# Headphone.net
KiCad netlist of a schematic drawn in EAGLE
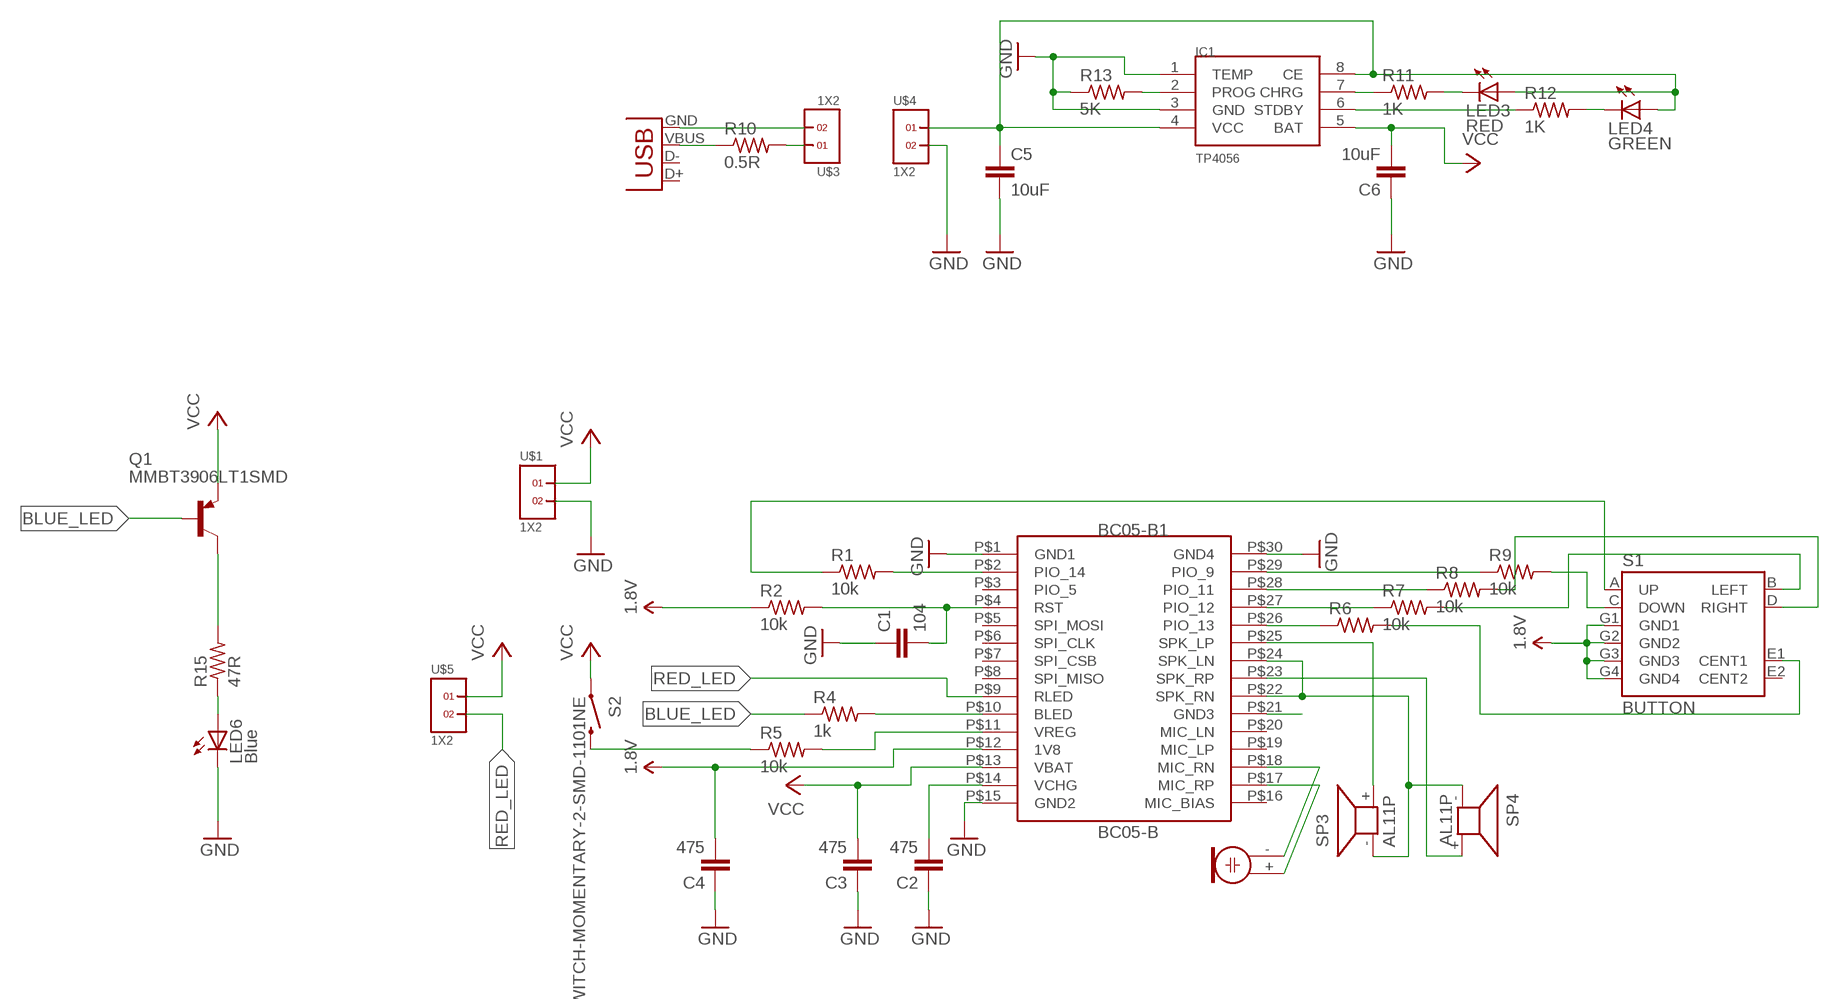
[diagram p0: schematic, sheet 1]

(export (version "E")
  (design (tool "Eeschema 10.0.6"))
  (components
    (comp (ref "BC05-B1")
      (value "BC05-B")
      (footprint "eagle-import:BC05-B")
      (libsource (lib "eagle-import") (part "BC05-B"))
    )
    (comp (ref "C1")
      (value "104")
      (footprint "eagle-import:C0603K")
      (libsource (lib "eagle-import") (part "C-EUC0603K"))
    )
    (comp (ref "C2")
      (value "475")
      (footprint "eagle-import:C0603K")
      (libsource (lib "eagle-import") (part "C-EUC0603K"))
    )
    (comp (ref "C3")
      (value "475")
      (footprint "eagle-import:C0603K")
      (libsource (lib "eagle-import") (part "C-EUC0603K"))
    )
    (comp (ref "C4")
      (value "475")
      (footprint "eagle-import:C0603K")
      (libsource (lib "eagle-import") (part "C-EUC0603K"))
    )
    (comp (ref "C5")
      (value "10uF")
      (footprint "eagle-import:C0805K")
      (libsource (lib "eagle-import") (part "C-EUC0805K"))
    )
    (comp (ref "C6")
      (value "10uF")
      (footprint "eagle-import:C0805K")
      (libsource (lib "eagle-import") (part "C-EUC0805K"))
    )
    (comp (ref "IC1")
      (value "TP4056")
      (footprint "eagle-import:SOP-8")
      (libsource (lib "eagle-import") (part "TP4056"))
    )
    (comp (ref "LED3")
      (value "RED")
      (footprint "eagle-import:CHIP-LED0805")
      (libsource (lib "eagle-import") (part "LEDCHIP-LED0805"))
    )
    (comp (ref "LED4")
      (value "GREEN")
      (footprint "eagle-import:CHIP-LED0805")
      (libsource (lib "eagle-import") (part "LEDCHIP-LED0805"))
    )
    (comp (ref "LED6")
      (value "Blue")
      (footprint "eagle-import:CHIP-LED0805")
      (libsource (lib "eagle-import") (part "LEDCHIP-LED0805"))
    )
    (comp (ref "M1")
      (value "ELECTRET_MICROPHON-TOM-1545P-R")
      (footprint "eagle-import:TOM-1545P-R")
      (libsource (lib "eagle-import") (part "ELECTRET_MICROPHON-TOM-1545P-R"))
    )
    (comp (ref "Q1")
      (value "MMBT3906LT1SMD")
      (footprint "eagle-import:SOT23-BEC")
      (libsource (lib "eagle-import") (part "MMBT3906SMDLT1"))
    )
    (comp (ref "R1")
      (value "10k")
      (footprint "eagle-import:R0603")
      (libsource (lib "eagle-import") (part "R-US_R0603"))
    )
    (comp (ref "R2")
      (value "10k")
      (footprint "eagle-import:R0603")
      (libsource (lib "eagle-import") (part "R-US_R0603"))
    )
    (comp (ref "R4")
      (value "1k")
      (footprint "eagle-import:R0603")
      (libsource (lib "eagle-import") (part "R-US_R0603"))
    )
    (comp (ref "R5")
      (value "10k")
      (footprint "eagle-import:R0603")
      (libsource (lib "eagle-import") (part "R-US_R0603"))
    )
    (comp (ref "R6")
      (value "10k")
      (footprint "eagle-import:R0603")
      (libsource (lib "eagle-import") (part "R-US_R0603"))
    )
    (comp (ref "R7")
      (value "10k")
      (footprint "eagle-import:R0603")
      (libsource (lib "eagle-import") (part "R-US_R0603"))
    )
    (comp (ref "R8")
      (value "10k")
      (footprint "eagle-import:R0603")
      (libsource (lib "eagle-import") (part "R-US_R0603"))
    )
    (comp (ref "R9")
      (value "10k")
      (footprint "eagle-import:R0603")
      (libsource (lib "eagle-import") (part "R-US_R0603"))
    )
    (comp (ref "R10")
      (value "0.5R")
      (footprint "eagle-import:M0805")
      (libsource (lib "eagle-import") (part "R-US_M0805"))
    )
    (comp (ref "R11")
      (value "1K")
      (footprint "eagle-import:R0603")
      (libsource (lib "eagle-import") (part "R-US_R0603"))
    )
    (comp (ref "R12")
      (value "1K")
      (footprint "eagle-import:R0603")
      (libsource (lib "eagle-import") (part "R-US_R0603"))
    )
    (comp (ref "R13")
      (value "5K")
      (footprint "eagle-import:R0603")
      (libsource (lib "eagle-import") (part "R-US_R0603"))
    )
    (comp (ref "R15")
      (value "47R")
      (footprint "eagle-import:R0603")
      (libsource (lib "eagle-import") (part "R-US_R0603"))
    )
    (comp (ref "S1")
      (value "BUTTON")
      (footprint "eagle-import:BUTTON")
      (libsource (lib "eagle-import") (part "BUTTON"))
    )
    (comp (ref "S2")
      (value "SWITCH-MOMENTARY-2-SMD-1101NE")
      (footprint "eagle-import:TACTILE-SWITCH-1101NE")
      (libsource (lib "eagle-import") (part "SWITCH-MOMENTARY-2-SMD-1101NE"))
    )
    (comp (ref "SP3")
      (value "AL11P")
      (footprint "eagle-import:AL11P")
      (libsource (lib "eagle-import") (part "AL11P"))
    )
    (comp (ref "SP4")
      (value "AL11P")
      (footprint "eagle-import:AL11P")
      (libsource (lib "eagle-import") (part "AL11P"))
    )
    (comp (ref "U$1")
      (value "1X2")
      (footprint "eagle-import:1X2")
      (libsource (lib "eagle-import") (part "1X2"))
    )
    (comp (ref "U$3")
      (value "1X2")
      (footprint "eagle-import:1X2")
      (libsource (lib "eagle-import") (part "1X2"))
    )
    (comp (ref "U$4")
      (value "1X2")
      (footprint "eagle-import:1X2")
      (libsource (lib "eagle-import") (part "1X2"))
    )
    (comp (ref "U$5")
      (value "1X2")
      (footprint "eagle-import:1X2")
      (libsource (lib "eagle-import") (part "1X2"))
    )
    (comp (ref "X1")
      (value "USB-MICROB")
      (footprint "eagle-import:USB-MICROB")
      (libsource (lib "eagle-import") (part "USB-MICROB"))
    )
  )
  (nets
    (net (code "1") (name "1.8V") (class "Default")
      (node (ref "BC05-B1") (pin "P$12") (pinfunction "1V8_P$12") (pintype "bidirectional"))
      (node (ref "C4") (pin "2") (pinfunction "2_2") (pintype "passive"))
      (node (ref "R2") (pin "1") (pinfunction "1_1") (pintype "passive"))
      (node (ref "S1") (pin "G1") (pinfunction "GND1_G1") (pintype "bidirectional"))
      (node (ref "S1") (pin "G2") (pinfunction "GND2_G2") (pintype "bidirectional"))
      (node (ref "S1") (pin "G3") (pinfunction "GND3_G3") (pintype "bidirectional"))
      (node (ref "S1") (pin "G4") (pinfunction "GND4_G4") (pintype "bidirectional"))
    )
    (net (code "2") (name "BLUE_LED") (class "Default")
      (node (ref "Q1") (pin "B") (pinfunction "B_B") (pintype "passive"))
      (node (ref "R4") (pin "1") (pinfunction "1_1") (pintype "passive"))
    )
    (net (code "3") (name "GND") (class "Default")
      (node (ref "BC05-B1") (pin "P$1") (pinfunction "GND1_P$1") (pintype "bidirectional"))
      (node (ref "BC05-B1") (pin "P$15") (pinfunction "GND2_P$15") (pintype "bidirectional"))
      (node (ref "BC05-B1") (pin "P$30") (pinfunction "GND4_P$30") (pintype "bidirectional"))
      (node (ref "C1") (pin "1") (pinfunction "1_1") (pintype "passive"))
      (node (ref "C2") (pin "1") (pinfunction "1_1") (pintype "passive"))
      (node (ref "C3") (pin "1") (pinfunction "1_1") (pintype "passive"))
      (node (ref "C4") (pin "1") (pinfunction "1_1") (pintype "passive"))
      (node (ref "C5") (pin "2") (pinfunction "2_2") (pintype "passive"))
      (node (ref "C6") (pin "1") (pinfunction "1_1") (pintype "passive"))
      (node (ref "IC1") (pin "1") (pinfunction "TEMP_1") (pintype "bidirectional"))
      (node (ref "IC1") (pin "3") (pinfunction "GND_3") (pintype "bidirectional"))
      (node (ref "LED6") (pin "C") (pinfunction "C_C") (pintype "passive"))
      (node (ref "R13") (pin "1") (pinfunction "1_1") (pintype "passive"))
      (node (ref "U$1") (pin "2") (pinfunction "2_2") (pintype "bidirectional"))
      (node (ref "U$4") (pin "2") (pinfunction "2_2") (pintype "bidirectional"))
    )
    (net (code "4") (name "Net-(BC05-B1-BLED)") (class "Default")
      (node (ref "BC05-B1") (pin "P$10") (pinfunction "BLED_P$10") (pintype "bidirectional"))
      (node (ref "R4") (pin "2") (pinfunction "2_2") (pintype "passive"))
    )
    (net (code "5") (name "Net-(BC05-B1-MIC_RN)") (class "Default")
      (node (ref "BC05-B1") (pin "P$18") (pinfunction "MIC_RN_P$18") (pintype "bidirectional"))
      (node (ref "M1") (pin "-") (pinfunction "2_-") (pintype "passive"))
    )
    (net (code "6") (name "Net-(BC05-B1-MIC_RP)") (class "Default")
      (node (ref "BC05-B1") (pin "P$17") (pinfunction "MIC_RP_P$17") (pintype "bidirectional"))
      (node (ref "M1") (pin "+") (pinfunction "1_+") (pintype "passive"))
    )
    (net (code "7") (name "Net-(BC05-B1-PIO_9)") (class "Default")
      (node (ref "BC05-B1") (pin "P$29") (pinfunction "PIO_9_P$29") (pintype "bidirectional"))
      (node (ref "R9") (pin "1") (pinfunction "1_1") (pintype "passive"))
    )
    (net (code "8") (name "Net-(BC05-B1-PIO_11)") (class "Default")
      (node (ref "BC05-B1") (pin "P$28") (pinfunction "PIO_11_P$28") (pintype "bidirectional"))
      (node (ref "R8") (pin "1") (pinfunction "1_1") (pintype "passive"))
    )
    (net (code "9") (name "Net-(BC05-B1-PIO_12)") (class "Default")
      (node (ref "BC05-B1") (pin "P$27") (pinfunction "PIO_12_P$27") (pintype "bidirectional"))
      (node (ref "R7") (pin "1") (pinfunction "1_1") (pintype "passive"))
    )
    (net (code "10") (name "Net-(BC05-B1-PIO_13)") (class "Default")
      (node (ref "BC05-B1") (pin "P$26") (pinfunction "PIO_13_P$26") (pintype "bidirectional"))
      (node (ref "R6") (pin "1") (pinfunction "1_1") (pintype "passive"))
    )
    (net (code "11") (name "Net-(BC05-B1-PIO_14)") (class "Default")
      (node (ref "BC05-B1") (pin "P$2") (pinfunction "PIO_14_P$2") (pintype "bidirectional"))
      (node (ref "R1") (pin "2") (pinfunction "2_2") (pintype "passive"))
    )
    (net (code "12") (name "Net-(BC05-B1-RST)") (class "Default")
      (node (ref "BC05-B1") (pin "P$4") (pinfunction "RST_P$4") (pintype "bidirectional"))
      (node (ref "C1") (pin "2") (pinfunction "2_2") (pintype "passive"))
      (node (ref "R2") (pin "2") (pinfunction "2_2") (pintype "passive"))
    )
    (net (code "13") (name "Net-(BC05-B1-SPK_LN)") (class "Default")
      (node (ref "BC05-B1") (pin "P$22") (pinfunction "SPK_RN_P$22") (pintype "bidirectional"))
      (node (ref "BC05-B1") (pin "P$24") (pinfunction "SPK_LN_P$24") (pintype "bidirectional"))
      (node (ref "SP3") (pin "-") (pinfunction "1_-") (pintype "passive"))
      (node (ref "SP4") (pin "-") (pinfunction "1_-") (pintype "passive"))
    )
    (net (code "14") (name "Net-(BC05-B1-SPK_LP)") (class "Default")
      (node (ref "BC05-B1") (pin "P$25") (pinfunction "SPK_LP_P$25") (pintype "bidirectional"))
      (node (ref "SP3") (pin "+") (pinfunction "2_+") (pintype "passive"))
    )
    (net (code "15") (name "Net-(BC05-B1-SPK_RP)") (class "Default")
      (node (ref "BC05-B1") (pin "P$23") (pinfunction "SPK_RP_P$23") (pintype "bidirectional"))
      (node (ref "SP4") (pin "+") (pinfunction "2_+") (pintype "passive"))
    )
    (net (code "16") (name "Net-(BC05-B1-VCHG)") (class "Default")
      (node (ref "BC05-B1") (pin "P$14") (pinfunction "VCHG_P$14") (pintype "bidirectional"))
      (node (ref "C2") (pin "2") (pinfunction "2_2") (pintype "passive"))
    )
    (net (code "17") (name "Net-(BC05-B1-VREG)") (class "Default")
      (node (ref "BC05-B1") (pin "P$11") (pinfunction "VREG_P$11") (pintype "bidirectional"))
      (node (ref "R5") (pin "2") (pinfunction "2_2") (pintype "passive"))
    )
    (net (code "18") (name "Net-(IC1-CE)") (class "Default")
      (node (ref "C5") (pin "1") (pinfunction "1_1") (pintype "passive"))
      (node (ref "IC1") (pin "4") (pinfunction "VCC_4") (pintype "bidirectional"))
      (node (ref "IC1") (pin "8") (pinfunction "CE_8") (pintype "bidirectional"))
      (node (ref "LED3") (pin "A") (pinfunction "A_A") (pintype "passive"))
      (node (ref "LED4") (pin "A") (pinfunction "A_A") (pintype "passive"))
      (node (ref "U$4") (pin "1") (pinfunction "1_1") (pintype "bidirectional"))
    )
    (net (code "19") (name "Net-(IC1-CHRG)") (class "Default")
      (node (ref "IC1") (pin "7") (pinfunction "CHRG_7") (pintype "bidirectional"))
      (node (ref "R11") (pin "1") (pinfunction "1_1") (pintype "passive"))
    )
    (net (code "20") (name "Net-(IC1-PROG)") (class "Default")
      (node (ref "IC1") (pin "2") (pinfunction "PROG_2") (pintype "bidirectional"))
      (node (ref "R13") (pin "2") (pinfunction "2_2") (pintype "passive"))
    )
    (net (code "21") (name "Net-(IC1-STDBY)") (class "Default")
      (node (ref "IC1") (pin "6") (pinfunction "STDBY_6") (pintype "bidirectional"))
      (node (ref "R12") (pin "1") (pinfunction "1_1") (pintype "passive"))
    )
    (net (code "22") (name "Net-(LED3-PadC)") (class "Default")
      (node (ref "LED3") (pin "C") (pinfunction "C_C") (pintype "passive"))
      (node (ref "R11") (pin "2") (pinfunction "2_2") (pintype "passive"))
    )
    (net (code "23") (name "Net-(LED4-PadC)") (class "Default")
      (node (ref "LED4") (pin "C") (pinfunction "C_C") (pintype "passive"))
      (node (ref "R12") (pin "2") (pinfunction "2_2") (pintype "passive"))
    )
    (net (code "24") (name "Net-(LED6-PadA)") (class "Default")
      (node (ref "LED6") (pin "A") (pinfunction "A_A") (pintype "passive"))
      (node (ref "R15") (pin "1") (pinfunction "1_1") (pintype "passive"))
    )
    (net (code "25") (name "Net-(Q1-PadC)") (class "Default")
      (node (ref "Q1") (pin "C") (pinfunction "C_C") (pintype "passive"))
      (node (ref "R15") (pin "2") (pinfunction "2_2") (pintype "passive"))
    )
    (net (code "26") (name "Net-(R10-Pad1)") (class "Default")
      (node (ref "R10") (pin "1") (pinfunction "1_1") (pintype "passive"))
      (node (ref "X1") (pin "VBUS") (pinfunction "VBUS_VBUS") (pintype "bidirectional"))
    )
    (net (code "27") (name "Net-(R10-Pad2)") (class "Default")
      (node (ref "R10") (pin "2") (pinfunction "2_2") (pintype "passive"))
      (node (ref "U$3") (pin "1") (pinfunction "1_1") (pintype "bidirectional"))
    )
    (net (code "28") (name "Net-(S1-CENT1)") (class "Default")
      (node (ref "R6") (pin "2") (pinfunction "2_2") (pintype "passive"))
      (node (ref "S1") (pin "E1") (pinfunction "CENT1_E1") (pintype "bidirectional"))
    )
    (net (code "29") (name "Net-(S1-DOWN)") (class "Default")
      (node (ref "R9") (pin "2") (pinfunction "2_2") (pintype "passive"))
      (node (ref "S1") (pin "C") (pinfunction "DOWN_C") (pintype "bidirectional"))
    )
    (net (code "30") (name "Net-(S1-LEFT)") (class "Default")
      (node (ref "R7") (pin "2") (pinfunction "2_2") (pintype "passive"))
      (node (ref "S1") (pin "B") (pinfunction "LEFT_B") (pintype "bidirectional"))
    )
    (net (code "31") (name "Net-(S1-RIGHT)") (class "Default")
      (node (ref "R8") (pin "2") (pinfunction "2_2") (pintype "passive"))
      (node (ref "S1") (pin "D") (pinfunction "RIGHT_D") (pintype "bidirectional"))
    )
    (net (code "32") (name "Net-(S1-UP)") (class "Default")
      (node (ref "R1") (pin "1") (pinfunction "1_1") (pintype "passive"))
      (node (ref "S1") (pin "A") (pinfunction "UP_A") (pintype "bidirectional"))
    )
    (net (code "33") (name "Net-(S2-2)") (class "Default")
      (node (ref "R5") (pin "1") (pinfunction "1_1") (pintype "passive"))
      (node (ref "S2") (pin "P$2") (pinfunction "2_P$2") (pintype "passive"))
    )
    (net (code "34") (name "Net-(U$3-Pad2)") (class "Default")
      (node (ref "U$3") (pin "2") (pinfunction "2_2") (pintype "bidirectional"))
      (node (ref "X1") (pin "GND") (pinfunction "GND_GND") (pintype "bidirectional"))
    )
    (net (code "35") (name "RED_LED") (class "Default")
      (node (ref "BC05-B1") (pin "P$9") (pinfunction "RLED_P$9") (pintype "bidirectional"))
      (node (ref "U$5") (pin "2") (pinfunction "2_2") (pintype "bidirectional"))
    )
    (net (code "36") (name "VCC") (class "Default")
      (node (ref "BC05-B1") (pin "P$13") (pinfunction "VBAT_P$13") (pintype "bidirectional"))
      (node (ref "C3") (pin "2") (pinfunction "2_2") (pintype "passive"))
      (node (ref "C6") (pin "2") (pinfunction "2_2") (pintype "passive"))
      (node (ref "IC1") (pin "5") (pinfunction "BAT_5") (pintype "bidirectional"))
      (node (ref "Q1") (pin "E") (pinfunction "E_E") (pintype "passive"))
      (node (ref "S2") (pin "P$1") (pinfunction "1_P$1") (pintype "passive"))
      (node (ref "U$1") (pin "1") (pinfunction "1_1") (pintype "bidirectional"))
      (node (ref "U$5") (pin "1") (pinfunction "1_1") (pintype "bidirectional"))
    )
    (net (code "37") (name "unconnected-(BC05-B1-GND3-PadP$21)") (class "Default")
      (node (ref "BC05-B1") (pin "P$21") (pinfunction "GND3_P$21") (pintype "bidirectional"))
    )
    (net (code "38") (name "unconnected-(BC05-B1-MIC_BIAS-PadP$16)") (class "Default")
      (node (ref "BC05-B1") (pin "P$16") (pinfunction "MIC_BIAS_P$16") (pintype "bidirectional"))
    )
    (net (code "39") (name "unconnected-(BC05-B1-MIC_LN-PadP$20)") (class "Default")
      (node (ref "BC05-B1") (pin "P$20") (pinfunction "MIC_LN_P$20") (pintype "bidirectional"))
    )
    (net (code "40") (name "unconnected-(BC05-B1-MIC_LP-PadP$19)") (class "Default")
      (node (ref "BC05-B1") (pin "P$19") (pinfunction "MIC_LP_P$19") (pintype "bidirectional"))
    )
    (net (code "41") (name "unconnected-(BC05-B1-PIO_5-PadP$3)") (class "Default")
      (node (ref "BC05-B1") (pin "P$3") (pinfunction "PIO_5_P$3") (pintype "bidirectional"))
    )
    (net (code "42") (name "unconnected-(BC05-B1-SPI_CLK-PadP$6)") (class "Default")
      (node (ref "BC05-B1") (pin "P$6") (pinfunction "SPI_CLK_P$6") (pintype "bidirectional"))
    )
    (net (code "43") (name "unconnected-(BC05-B1-SPI_CSB-PadP$7)") (class "Default")
      (node (ref "BC05-B1") (pin "P$7") (pinfunction "SPI_CSB_P$7") (pintype "bidirectional"))
    )
    (net (code "44") (name "unconnected-(BC05-B1-SPI_MISO-PadP$8)") (class "Default")
      (node (ref "BC05-B1") (pin "P$8") (pinfunction "SPI_MISO_P$8") (pintype "bidirectional"))
    )
    (net (code "45") (name "unconnected-(BC05-B1-SPI_MOSI-PadP$5)") (class "Default")
      (node (ref "BC05-B1") (pin "P$5") (pinfunction "SPI_MOSI_P$5") (pintype "bidirectional"))
    )
    (net (code "46") (name "unconnected-(S1-CENT2-PadE2)") (class "Default")
      (node (ref "S1") (pin "E2") (pinfunction "CENT2_E2") (pintype "bidirectional"))
    )
    (net (code "47") (name "unconnected-(X1-PadD+)") (class "Default")
      (node (ref "X1") (pin "D+") (pinfunction "D+_D+") (pintype "bidirectional"))
    )
    (net (code "48") (name "unconnected-(X1-PadD-)") (class "Default")
      (node (ref "X1") (pin "D-") (pinfunction "D-_D-") (pintype "bidirectional"))
    )
  )
)
